# SAO_Genie.net
KiCad netlist of a schematic drawn in EAGLE
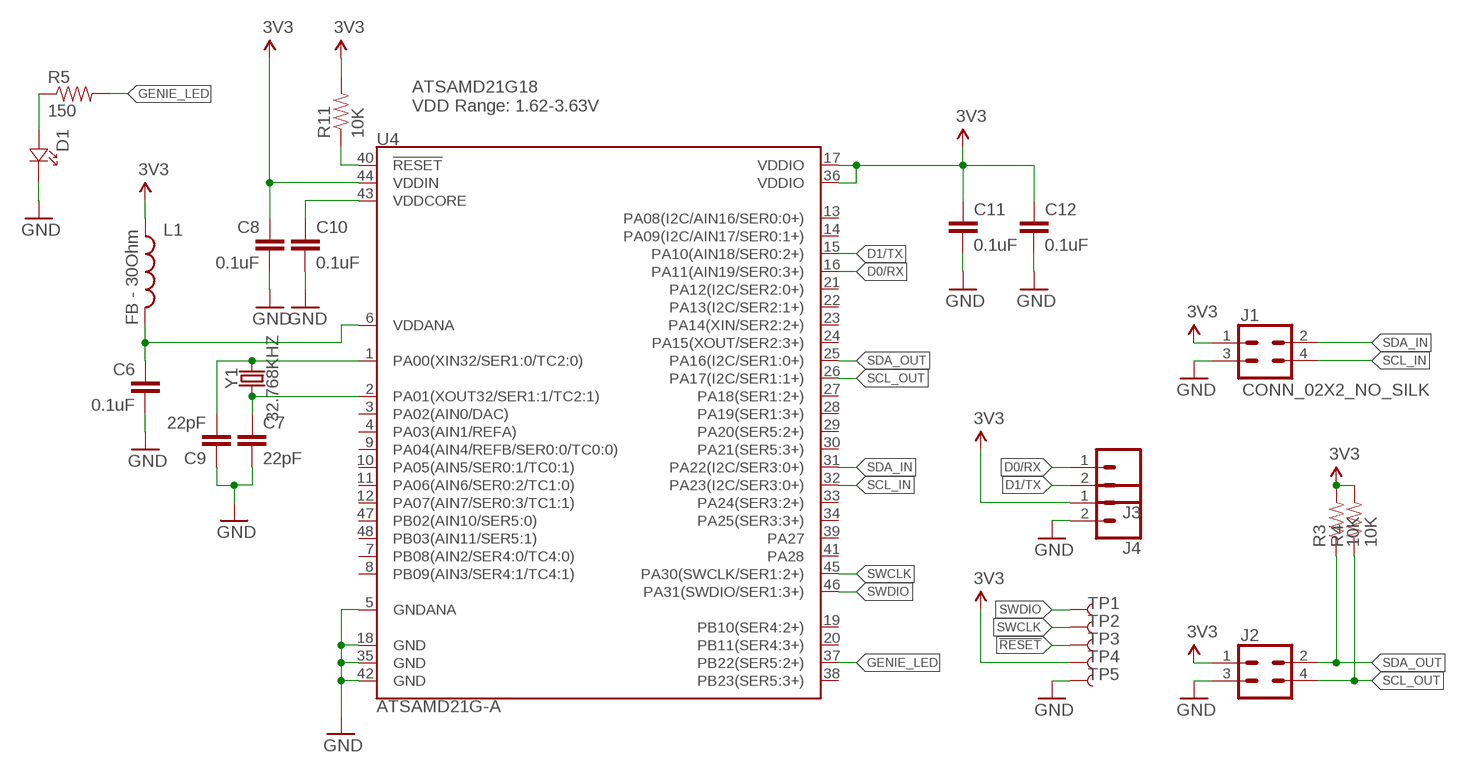
[diagram p0: schematic, sheet 1]

(export (version "E")
  (design (tool "Eeschema 10.0.6"))
  (components
    (comp (ref "C6")
      (value "0.1uF")
      (footprint "eagle-import:0603-CAP")
      (libsource (lib "eagle-import") (part "0.1UF-25V(+80/-20%)(0603)"))
    )
    (comp (ref "C7")
      (value "22pF")
      (footprint "eagle-import:0603-CAP")
      (libsource (lib "eagle-import") (part "15PF-50V-5%(0603)"))
    )
    (comp (ref "C8")
      (value "0.1uF")
      (footprint "eagle-import:0603-CAP")
      (libsource (lib "eagle-import") (part "0.1UF-25V(+80/-20%)(0603)"))
    )
    (comp (ref "C9")
      (value "22pF")
      (footprint "eagle-import:0603-CAP")
      (libsource (lib "eagle-import") (part "15PF-50V-5%(0603)"))
    )
    (comp (ref "C10")
      (value "0.1uF")
      (footprint "eagle-import:0603-CAP")
      (libsource (lib "eagle-import") (part "0.1UF-25V(+80/-20%)(0603)"))
    )
    (comp (ref "C11")
      (value "0.1uF")
      (footprint "eagle-import:0603-CAP")
      (libsource (lib "eagle-import") (part "0.1UF-25V(+80/-20%)(0603)"))
    )
    (comp (ref "C12")
      (value "0.1uF")
      (footprint "eagle-import:0603-CAP")
      (libsource (lib "eagle-import") (part "0.1UF-25V(+80/-20%)(0603)"))
    )
    (comp (ref "D1")
      (value "LED1206REVERSE_NO_SILK")
      (footprint "eagle-import:1206_NO_SILK")
      (libsource (lib "eagle-import") (part "LED1206REVERSE_NO_SILK"))
    )
    (comp (ref "J1")
      (value "CONN_02X2_NO_SILK")
      (footprint "eagle-import:2X2_NO_SILK")
      (libsource (lib "eagle-import") (part "CONN_02X2_NO_SILK"))
    )
    (comp (ref "J2")
      (value "SAO OUT")
      (footprint "eagle-import:2X2_NO_SILK")
      (libsource (lib "eagle-import") (part "CONN_02X2_NO_SILK"))
    )
    (comp (ref "J3")
      (value "CONN_021X02_NO_SILK")
      (footprint "eagle-import:1X02_NO_SILK")
      (libsource (lib "eagle-import") (part "CONN_021X02_NO_SILK"))
    )
    (comp (ref "J4")
      (value "CONN_021X02_NO_SILK")
      (footprint "eagle-import:1X02_NO_SILK")
      (libsource (lib "eagle-import") (part "CONN_021X02_NO_SILK"))
    )
    (comp (ref "L1")
      (value "FB - 30Ohm")
      (footprint "eagle-import:0603")
      (libsource (lib "eagle-import") (part "INDUCTOR0603"))
    )
    (comp (ref "R3")
      (value "10K")
      (footprint "eagle-import:0603-RES")
      (libsource (lib "eagle-import") (part "10KOHM-1/10W-1%(0603)0603"))
    )
    (comp (ref "R4")
      (value "10K")
      (footprint "eagle-import:0603-RES")
      (libsource (lib "eagle-import") (part "10KOHM-1/10W-1%(0603)0603"))
    )
    (comp (ref "R5")
      (value "150")
      (footprint "eagle-import:0603-RES")
      (libsource (lib "eagle-import") (part "10KOHM-1/10W-1%(0603)0603"))
    )
    (comp (ref "R11")
      (value "10K")
      (footprint "eagle-import:0603-RES")
      (libsource (lib "eagle-import") (part "10KOHM-1/10W-1%(0603)0603"))
    )
    (comp (ref "TP1")
      (value "TEST-POINT3X5")
      (footprint "eagle-import:PAD.03X.05")
      (libsource (lib "eagle-import") (part "TEST-POINT3X5"))
    )
    (comp (ref "TP2")
      (value "TEST-POINT3X5")
      (footprint "eagle-import:PAD.03X.05")
      (libsource (lib "eagle-import") (part "TEST-POINT3X5"))
    )
    (comp (ref "TP3")
      (value "TEST-POINT3X5")
      (footprint "eagle-import:PAD.03X.05")
      (libsource (lib "eagle-import") (part "TEST-POINT3X5"))
    )
    (comp (ref "TP4")
      (value "TEST-POINT3X5")
      (footprint "eagle-import:PAD.03X.05")
      (libsource (lib "eagle-import") (part "TEST-POINT3X5"))
    )
    (comp (ref "TP5")
      (value "TEST-POINT3X5")
      (footprint "eagle-import:PAD.03X.05")
      (libsource (lib "eagle-import") (part "TEST-POINT3X5"))
    )
    (comp (ref "U4")
      (value "ATSAMD21G-A")
      (footprint "eagle-import:TQFP-48")
      (libsource (lib "eagle-import") (part "ATSAMD21G-A"))
    )
    (comp (ref "Y1")
      (value "32.768KHZ")
      (footprint "eagle-import:ABS06")
      (libsource (lib "eagle-import") (part "ABS06-127-32.768KHZ"))
    )
  )
  (nets
    (net (code "1") (name "/~{RESET}") (class "Default")
      (node (ref "R11") (pin "1") (pinfunction "1_1") (pintype "passive"))
      (node (ref "TP3") (pin "P$1") (pinfunction "1_P$1") (pintype "bidirectional"))
      (node (ref "U4") (pin "40") (pinfunction "~{RESET}_40") (pintype "bidirectional"))
    )
    (net (code "2") (name "3V3") (class "Default")
      (node (ref "C11") (pin "1") (pinfunction "1_1") (pintype "passive"))
      (node (ref "C12") (pin "1") (pinfunction "1_1") (pintype "passive"))
      (node (ref "C8") (pin "1") (pinfunction "1_1") (pintype "passive"))
      (node (ref "J1") (pin "1") (pinfunction "1_1") (pintype "bidirectional"))
      (node (ref "J2") (pin "1") (pinfunction "1_1") (pintype "bidirectional"))
      (node (ref "J4") (pin "1") (pinfunction "1_1") (pintype "passive"))
      (node (ref "L1") (pin "1") (pinfunction "1_1") (pintype "passive"))
      (node (ref "R11") (pin "2") (pinfunction "2_2") (pintype "passive"))
      (node (ref "R3") (pin "2") (pinfunction "2_2") (pintype "passive"))
      (node (ref "R4") (pin "2") (pinfunction "2_2") (pintype "passive"))
      (node (ref "TP4") (pin "P$1") (pinfunction "1_P$1") (pintype "bidirectional"))
      (node (ref "U4") (pin "17") (pinfunction "VDDIO_17") (pintype "bidirectional"))
      (node (ref "U4") (pin "36") (pinfunction "VDDIO_36") (pintype "bidirectional"))
      (node (ref "U4") (pin "44") (pinfunction "VDDIN_44") (pintype "bidirectional"))
    )
    (net (code "3") (name "D0{slash}RX") (class "Default")
      (node (ref "J3") (pin "1") (pinfunction "1_1") (pintype "passive"))
      (node (ref "U4") (pin "16") (pinfunction "PA11(AIN19/SER0:3+)_16") (pintype "bidirectional"))
    )
    (net (code "4") (name "D1{slash}TX") (class "Default")
      (node (ref "J3") (pin "2") (pinfunction "2_2") (pintype "passive"))
      (node (ref "U4") (pin "15") (pinfunction "PA10(AIN18/SER0:2+)_15") (pintype "bidirectional"))
    )
    (net (code "5") (name "GENIE_LED") (class "Default")
      (node (ref "R5") (pin "2") (pinfunction "2_2") (pintype "passive"))
      (node (ref "U4") (pin "37") (pinfunction "PB22(SER5:2+)_37") (pintype "bidirectional"))
    )
    (net (code "6") (name "GND") (class "Default")
      (node (ref "C10") (pin "2") (pinfunction "2_2") (pintype "passive"))
      (node (ref "C11") (pin "2") (pinfunction "2_2") (pintype "passive"))
      (node (ref "C12") (pin "2") (pinfunction "2_2") (pintype "passive"))
      (node (ref "C6") (pin "2") (pinfunction "2_2") (pintype "passive"))
      (node (ref "C7") (pin "2") (pinfunction "2_2") (pintype "passive"))
      (node (ref "C8") (pin "2") (pinfunction "2_2") (pintype "passive"))
      (node (ref "C9") (pin "1") (pinfunction "1_1") (pintype "passive"))
      (node (ref "D1") (pin "P$1") (pinfunction "P$2_P$1") (pintype "bidirectional"))
      (node (ref "J1") (pin "3") (pinfunction "3_3") (pintype "bidirectional"))
      (node (ref "J2") (pin "3") (pinfunction "3_3") (pintype "bidirectional"))
      (node (ref "J4") (pin "2") (pinfunction "2_2") (pintype "passive"))
      (node (ref "TP5") (pin "P$1") (pinfunction "1_P$1") (pintype "bidirectional"))
      (node (ref "U4") (pin "18") (pinfunction "GND_18") (pintype "bidirectional"))
      (node (ref "U4") (pin "35") (pinfunction "GND_35") (pintype "bidirectional"))
      (node (ref "U4") (pin "42") (pinfunction "GND_42") (pintype "bidirectional"))
      (node (ref "U4") (pin "5") (pinfunction "GNDANA_5") (pintype "bidirectional"))
    )
    (net (code "7") (name "Net-(D1-P$1)") (class "Default")
      (node (ref "D1") (pin "P$2") (pinfunction "P$1_P$2") (pintype "bidirectional"))
      (node (ref "R5") (pin "1") (pinfunction "1_1") (pintype "passive"))
    )
    (net (code "8") (name "Net-(U4-PA00(XIN32{slash}SER1:0{slash}TC2:0))") (class "Default")
      (node (ref "C9") (pin "2") (pinfunction "2_2") (pintype "passive"))
      (node (ref "U4") (pin "1") (pinfunction "PA00(XIN32/SER1:0/TC2:0)_1") (pintype "bidirectional"))
      (node (ref "Y1") (pin "P$2") (pinfunction "2_P$2") (pintype "passive"))
    )
    (net (code "9") (name "Net-(U4-PA01(XOUT32{slash}SER1:1{slash}TC2:1))") (class "Default")
      (node (ref "C7") (pin "1") (pinfunction "1_1") (pintype "passive"))
      (node (ref "U4") (pin "2") (pinfunction "PA01(XOUT32/SER1:1/TC2:1)_2") (pintype "bidirectional"))
      (node (ref "Y1") (pin "P$1") (pinfunction "1_P$1") (pintype "passive"))
    )
    (net (code "10") (name "Net-(U4-VDDANA)") (class "Default")
      (node (ref "C6") (pin "1") (pinfunction "1_1") (pintype "passive"))
      (node (ref "L1") (pin "2") (pinfunction "2_2") (pintype "passive"))
      (node (ref "U4") (pin "6") (pinfunction "VDDANA_6") (pintype "bidirectional"))
    )
    (net (code "11") (name "Net-(U4-VDDCORE)") (class "Default")
      (node (ref "C10") (pin "1") (pinfunction "1_1") (pintype "passive"))
      (node (ref "U4") (pin "43") (pinfunction "VDDCORE_43") (pintype "bidirectional"))
    )
    (net (code "12") (name "SCL_IN") (class "Default")
      (node (ref "J1") (pin "4") (pinfunction "4_4") (pintype "bidirectional"))
      (node (ref "U4") (pin "32") (pinfunction "PA23(I2C/SER3:0+)_32") (pintype "bidirectional"))
    )
    (net (code "13") (name "SCL_OUT") (class "Default")
      (node (ref "J2") (pin "4") (pinfunction "4_4") (pintype "bidirectional"))
      (node (ref "R4") (pin "1") (pinfunction "1_1") (pintype "passive"))
      (node (ref "U4") (pin "26") (pinfunction "PA17(I2C/SER1:1+)_26") (pintype "bidirectional"))
    )
    (net (code "14") (name "SDA_IN") (class "Default")
      (node (ref "J1") (pin "2") (pinfunction "2_2") (pintype "bidirectional"))
      (node (ref "U4") (pin "31") (pinfunction "PA22(I2C/SER3:0+)_31") (pintype "bidirectional"))
    )
    (net (code "15") (name "SDA_OUT") (class "Default")
      (node (ref "J2") (pin "2") (pinfunction "2_2") (pintype "bidirectional"))
      (node (ref "R3") (pin "1") (pinfunction "1_1") (pintype "passive"))
      (node (ref "U4") (pin "25") (pinfunction "PA16(I2C/SER1:0+)_25") (pintype "bidirectional"))
    )
    (net (code "16") (name "SWCLK") (class "Default")
      (node (ref "TP2") (pin "P$1") (pinfunction "1_P$1") (pintype "bidirectional"))
      (node (ref "U4") (pin "45") (pinfunction "PA30(SWCLK/SER1:2+)_45") (pintype "bidirectional"))
    )
    (net (code "17") (name "SWDIO") (class "Default")
      (node (ref "TP1") (pin "P$1") (pinfunction "1_P$1") (pintype "bidirectional"))
      (node (ref "U4") (pin "46") (pinfunction "PA31(SWDIO/SER1:3+)_46") (pintype "bidirectional"))
    )
    (net (code "18") (name "unconnected-(U4-PA02(AIN0{slash}DAC)-Pad3)") (class "Default")
      (node (ref "U4") (pin "3") (pinfunction "PA02(AIN0/DAC)_3") (pintype "bidirectional"))
    )
    (net (code "19") (name "unconnected-(U4-PA03(AIN1{slash}REFA)-Pad4)") (class "Default")
      (node (ref "U4") (pin "4") (pinfunction "PA03(AIN1/REFA)_4") (pintype "bidirectional"))
    )
    (net (code "20") (name "unconnected-(U4-PA04(AIN4{slash}REFB{slash}SER0:0{slash}TC0:0)-Pad9)") (class "Default")
      (node (ref "U4") (pin "9") (pinfunction "PA04(AIN4/REFB/SER0:0/TC0:0)_9") (pintype "bidirectional"))
    )
    (net (code "21") (name "unconnected-(U4-PA05(AIN5{slash}SER0:1{slash}TC0:1)-Pad10)") (class "Default")
      (node (ref "U4") (pin "10") (pinfunction "PA05(AIN5/SER0:1/TC0:1)_10") (pintype "bidirectional"))
    )
    (net (code "22") (name "unconnected-(U4-PA06(AIN6{slash}SER0:2{slash}TC1:0)-Pad11)") (class "Default")
      (node (ref "U4") (pin "11") (pinfunction "PA06(AIN6/SER0:2/TC1:0)_11") (pintype "bidirectional"))
    )
    (net (code "23") (name "unconnected-(U4-PA07(AIN7{slash}SER0:3{slash}TC1:1)-Pad12)") (class "Default")
      (node (ref "U4") (pin "12") (pinfunction "PA07(AIN7/SER0:3/TC1:1)_12") (pintype "bidirectional"))
    )
    (net (code "24") (name "unconnected-(U4-PA08(I2C{slash}AIN16{slash}SER0:0+)-Pad13)") (class "Default")
      (node (ref "U4") (pin "13") (pinfunction "PA08(I2C/AIN16/SER0:0+)_13") (pintype "bidirectional"))
    )
    (net (code "25") (name "unconnected-(U4-PA09(I2C{slash}AIN17{slash}SER0:1+)-Pad14)") (class "Default")
      (node (ref "U4") (pin "14") (pinfunction "PA09(I2C/AIN17/SER0:1+)_14") (pintype "bidirectional"))
    )
    (net (code "26") (name "unconnected-(U4-PA12(I2C{slash}SER2:0+)-Pad21)") (class "Default")
      (node (ref "U4") (pin "21") (pinfunction "PA12(I2C/SER2:0+)_21") (pintype "bidirectional"))
    )
    (net (code "27") (name "unconnected-(U4-PA13(I2C{slash}SER2:1+)-Pad22)") (class "Default")
      (node (ref "U4") (pin "22") (pinfunction "PA13(I2C/SER2:1+)_22") (pintype "bidirectional"))
    )
    (net (code "28") (name "unconnected-(U4-PA14(XIN{slash}SER2:2+)-Pad23)") (class "Default")
      (node (ref "U4") (pin "23") (pinfunction "PA14(XIN/SER2:2+)_23") (pintype "bidirectional"))
    )
    (net (code "29") (name "unconnected-(U4-PA15(XOUT{slash}SER2:3+)-Pad24)") (class "Default")
      (node (ref "U4") (pin "24") (pinfunction "PA15(XOUT/SER2:3+)_24") (pintype "bidirectional"))
    )
    (net (code "30") (name "unconnected-(U4-PA18(SER1:2+)-Pad27)") (class "Default")
      (node (ref "U4") (pin "27") (pinfunction "PA18(SER1:2+)_27") (pintype "bidirectional"))
    )
    (net (code "31") (name "unconnected-(U4-PA19(SER1:3+)-Pad28)") (class "Default")
      (node (ref "U4") (pin "28") (pinfunction "PA19(SER1:3+)_28") (pintype "bidirectional"))
    )
    (net (code "32") (name "unconnected-(U4-PA20(SER5:2+)-Pad29)") (class "Default")
      (node (ref "U4") (pin "29") (pinfunction "PA20(SER5:2+)_29") (pintype "bidirectional"))
    )
    (net (code "33") (name "unconnected-(U4-PA21(SER5:3+)-Pad30)") (class "Default")
      (node (ref "U4") (pin "30") (pinfunction "PA21(SER5:3+)_30") (pintype "bidirectional"))
    )
    (net (code "34") (name "unconnected-(U4-PA24(SER3:2+)-Pad33)") (class "Default")
      (node (ref "U4") (pin "33") (pinfunction "PA24(SER3:2+)_33") (pintype "bidirectional"))
    )
    (net (code "35") (name "unconnected-(U4-PA25(SER3:3+)-Pad34)") (class "Default")
      (node (ref "U4") (pin "34") (pinfunction "PA25(SER3:3+)_34") (pintype "bidirectional"))
    )
    (net (code "36") (name "unconnected-(U4-PA27-Pad39)") (class "Default")
      (node (ref "U4") (pin "39") (pinfunction "PA27_39") (pintype "bidirectional"))
    )
    (net (code "37") (name "unconnected-(U4-PA28-Pad41)") (class "Default")
      (node (ref "U4") (pin "41") (pinfunction "PA28_41") (pintype "bidirectional"))
    )
    (net (code "38") (name "unconnected-(U4-PB02(AIN10{slash}SER5:0)-Pad47)") (class "Default")
      (node (ref "U4") (pin "47") (pinfunction "PB02(AIN10/SER5:0)_47") (pintype "bidirectional"))
    )
    (net (code "39") (name "unconnected-(U4-PB03(AIN11{slash}SER5:1)-Pad48)") (class "Default")
      (node (ref "U4") (pin "48") (pinfunction "PB03(AIN11/SER5:1)_48") (pintype "bidirectional"))
    )
    (net (code "40") (name "unconnected-(U4-PB08(AIN2{slash}SER4:0{slash}TC4:0)-Pad7)") (class "Default")
      (node (ref "U4") (pin "7") (pinfunction "PB08(AIN2/SER4:0/TC4:0)_7") (pintype "bidirectional"))
    )
    (net (code "41") (name "unconnected-(U4-PB09(AIN3{slash}SER4:1{slash}TC4:1)-Pad8)") (class "Default")
      (node (ref "U4") (pin "8") (pinfunction "PB09(AIN3/SER4:1/TC4:1)_8") (pintype "bidirectional"))
    )
    (net (code "42") (name "unconnected-(U4-PB10(SER4:2+)-Pad19)") (class "Default")
      (node (ref "U4") (pin "19") (pinfunction "PB10(SER4:2+)_19") (pintype "bidirectional"))
    )
    (net (code "43") (name "unconnected-(U4-PB11(SER4:3+)-Pad20)") (class "Default")
      (node (ref "U4") (pin "20") (pinfunction "PB11(SER4:3+)_20") (pintype "bidirectional"))
    )
    (net (code "44") (name "unconnected-(U4-PB23(SER5:3+)-Pad38)") (class "Default")
      (node (ref "U4") (pin "38") (pinfunction "PB23(SER5:3+)_38") (pintype "bidirectional"))
    )
  )
)
